# deska.net
KiCad netlist of a schematic drawn in EAGLE
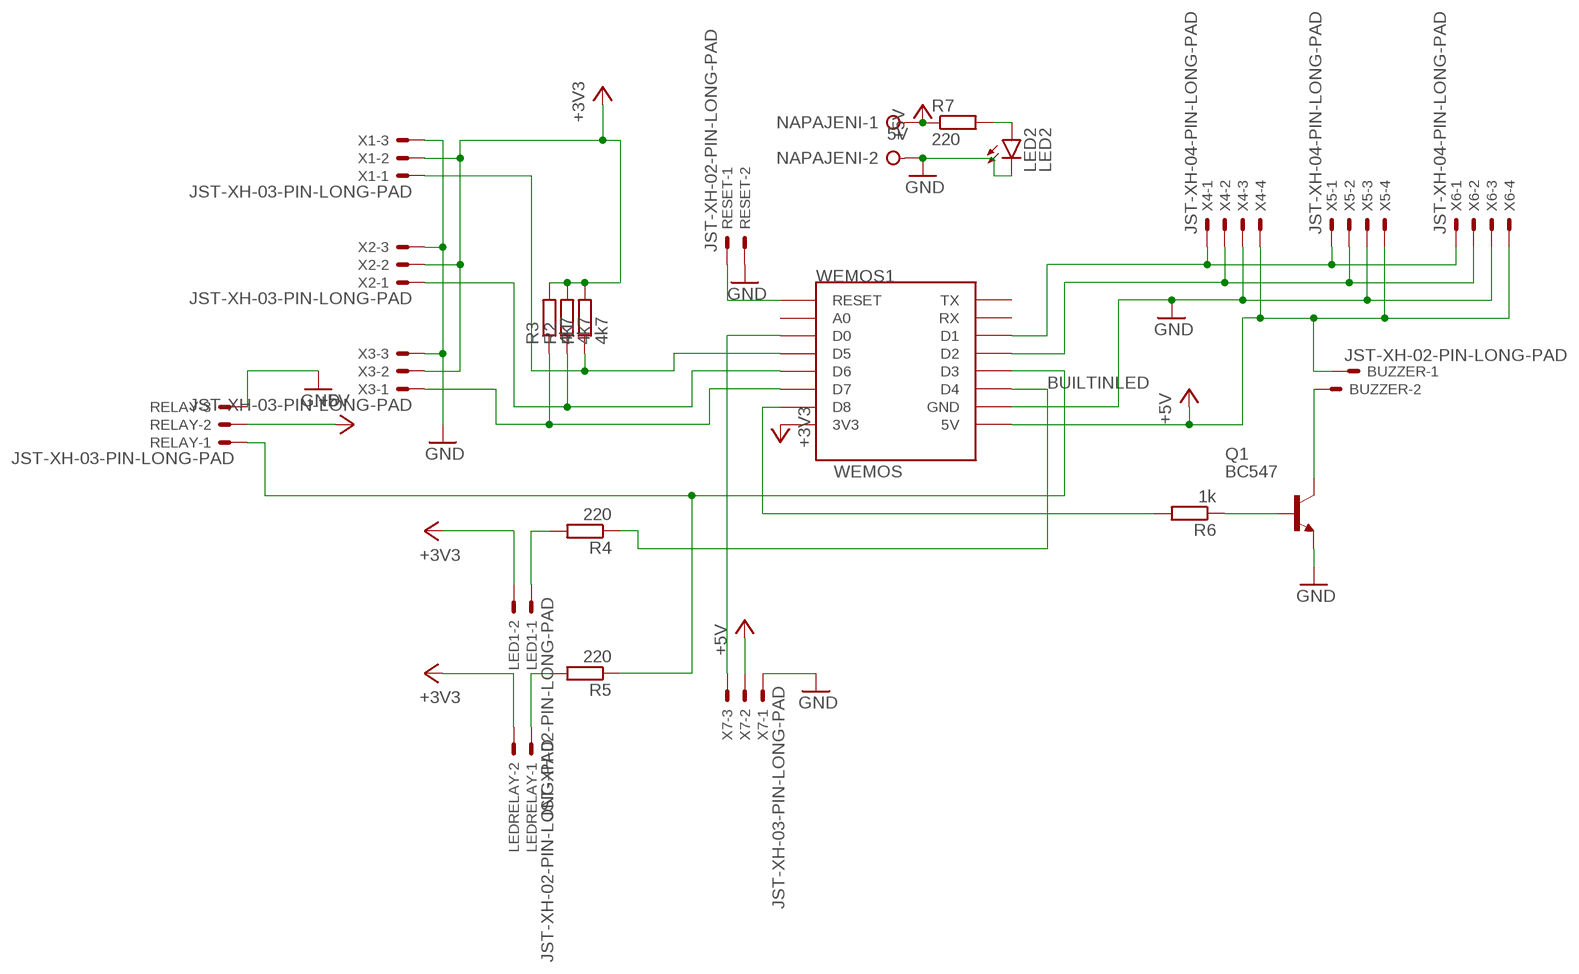
[diagram p0: schematic, sheet 1]

(export (version "E")
  (design (tool "Eeschema 10.0.6"))
  (components
    (comp (ref "BUZZER")
      (value "JST-XH-02-PIN-LONG-PAD")
      (footprint "eagle-import:JST-XH-02-PACKAGE-LONG-PAD")
      (libsource (lib "eagle-import") (part "JST-XH-02-PIN-LONG-PAD"))
    )
    (comp (ref "LED1")
      (value "JST-XH-02-PIN-LONG-PAD")
      (footprint "eagle-import:JST-XH-02-PACKAGE-LONG-PAD")
      (libsource (lib "eagle-import") (part "JST-XH-02-PIN-LONG-PAD"))
    )
    (comp (ref "LED2")
      (value "LED2")
      (footprint "eagle-import:LED3MM")
      (libsource (lib "eagle-import") (part "LED3MM"))
    )
    (comp (ref "LEDRELAY")
      (value "JST-XH-02-PIN-LONG-PAD")
      (footprint "eagle-import:JST-XH-02-PACKAGE-LONG-PAD")
      (libsource (lib "eagle-import") (part "JST-XH-02-PIN-LONG-PAD"))
    )
    (comp (ref "NAPAJENI")
      (value "5V")
      (footprint "eagle-import:W237-132")
      (libsource (lib "eagle-import") (part "W237-02P"))
    )
    (comp (ref "Q1")
      (value "BC547")
      (footprint "eagle-import:TO92")
      (libsource (lib "eagle-import") (part "BC547"))
    )
    (comp (ref "R1")
      (value "4k7")
      (footprint "eagle-import:0207_7")
      (libsource (lib "eagle-import") (part "R-EU_0207/7"))
    )
    (comp (ref "R2")
      (value "4k7")
      (footprint "eagle-import:0207_7")
      (libsource (lib "eagle-import") (part "R-EU_0207/7"))
    )
    (comp (ref "R3")
      (value "4k7")
      (footprint "eagle-import:0207_7")
      (libsource (lib "eagle-import") (part "R-EU_0207/7"))
    )
    (comp (ref "R4")
      (value "220")
      (footprint "eagle-import:0207_7")
      (libsource (lib "eagle-import") (part "R-EU_0207/7"))
    )
    (comp (ref "R5")
      (value "220")
      (footprint "eagle-import:0207_7")
      (libsource (lib "eagle-import") (part "R-EU_0207/7"))
    )
    (comp (ref "R6")
      (value "1k")
      (footprint "eagle-import:0207_7")
      (libsource (lib "eagle-import") (part "R-EU_0207/7"))
    )
    (comp (ref "R7")
      (value "220")
      (footprint "eagle-import:0207_7")
      (libsource (lib "eagle-import") (part "R-EU_0207/7"))
    )
    (comp (ref "RELAY")
      (value "JST-XH-03-PIN-LONG-PAD")
      (footprint "eagle-import:JST-XH-03-PACKAGE-LONG-PAD")
      (libsource (lib "eagle-import") (part "JST-XH-03-PIN-LONG-PAD"))
    )
    (comp (ref "RESET")
      (value "JST-XH-02-PIN-LONG-PAD")
      (footprint "eagle-import:JST-XH-02-PACKAGE-LONG-PAD")
      (libsource (lib "eagle-import") (part "JST-XH-02-PIN-LONG-PAD"))
    )
    (comp (ref "WEMOS1")
      (value "WEMOS")
      (footprint "eagle-import:WEMOS-D1-MINI")
      (libsource (lib "eagle-import") (part "WEMOS-D1-MINI"))
    )
    (comp (ref "X1")
      (value "JST-XH-03-PIN-LONG-PAD")
      (footprint "eagle-import:JST-XH-03-PACKAGE-LONG-PAD")
      (libsource (lib "eagle-import") (part "JST-XH-03-PIN-LONG-PAD"))
    )
    (comp (ref "X2")
      (value "JST-XH-03-PIN-LONG-PAD")
      (footprint "eagle-import:JST-XH-03-PACKAGE-LONG-PAD")
      (libsource (lib "eagle-import") (part "JST-XH-03-PIN-LONG-PAD"))
    )
    (comp (ref "X3")
      (value "JST-XH-03-PIN-LONG-PAD")
      (footprint "eagle-import:JST-XH-03-PACKAGE-LONG-PAD")
      (libsource (lib "eagle-import") (part "JST-XH-03-PIN-LONG-PAD"))
    )
    (comp (ref "X4")
      (value "JST-XH-04-PIN-LONG-PAD")
      (footprint "eagle-import:JST-XH-04-PACKAGE-LONG-PAD")
      (libsource (lib "eagle-import") (part "JST-XH-04-PIN-LONG-PAD"))
    )
    (comp (ref "X5")
      (value "JST-XH-04-PIN-LONG-PAD")
      (footprint "eagle-import:JST-XH-04-PACKAGE-LONG-PAD")
      (libsource (lib "eagle-import") (part "JST-XH-04-PIN-LONG-PAD"))
    )
    (comp (ref "X6")
      (value "JST-XH-04-PIN-LONG-PAD")
      (footprint "eagle-import:JST-XH-04-PACKAGE-LONG-PAD")
      (libsource (lib "eagle-import") (part "JST-XH-04-PIN-LONG-PAD"))
    )
    (comp (ref "X7")
      (value "JST-XH-03-PIN-LONG-PAD")
      (footprint "eagle-import:JST-XH-03-PACKAGE-LONG-PAD")
      (libsource (lib "eagle-import") (part "JST-XH-03-PIN-LONG-PAD"))
    )
  )
  (nets
    (net (code "1") (name "+3V3") (class "Default")
      (node (ref "LED1") (pin "2") (pinfunction "S_2") (pintype "passive"))
      (node (ref "LEDRELAY") (pin "2") (pinfunction "S_2") (pintype "passive"))
      (node (ref "R1") (pin "2") (pinfunction "2_2") (pintype "passive"))
      (node (ref "R2") (pin "2") (pinfunction "2_2") (pintype "passive"))
      (node (ref "R3") (pin "2") (pinfunction "2_2") (pintype "passive"))
      (node (ref "WEMOS1") (pin "3V3") (pinfunction "3V3_3V3") (pintype "bidirectional"))
      (node (ref "X1") (pin "2") (pinfunction "S_2") (pintype "passive"))
      (node (ref "X2") (pin "2") (pinfunction "S_2") (pintype "passive"))
      (node (ref "X3") (pin "2") (pinfunction "S_2") (pintype "passive"))
    )
    (net (code "2") (name "+5V") (class "Default")
      (node (ref "BUZZER") (pin "1") (pinfunction "S_1") (pintype "passive"))
      (node (ref "NAPAJENI") (pin "1") (pinfunction "KL_1") (pintype "passive"))
      (node (ref "R7") (pin "1") (pinfunction "1_1") (pintype "passive"))
      (node (ref "RELAY") (pin "2") (pinfunction "S_2") (pintype "passive"))
      (node (ref "WEMOS1") (pin "5V") (pinfunction "5V_5V") (pintype "bidirectional"))
      (node (ref "X4") (pin "4") (pinfunction "S_4") (pintype "passive"))
      (node (ref "X5") (pin "4") (pinfunction "S_4") (pintype "passive"))
      (node (ref "X6") (pin "4") (pinfunction "S_4") (pintype "passive"))
      (node (ref "X7") (pin "2") (pinfunction "S_2") (pintype "passive"))
    )
    (net (code "3") (name "/BUILTINLED") (class "Default")
      (node (ref "R4") (pin "1") (pinfunction "1_1") (pintype "passive"))
      (node (ref "WEMOS1") (pin "D4") (pinfunction "D4_D4") (pintype "bidirectional"))
    )
    (net (code "4") (name "GND") (class "Default")
      (node (ref "LED2") (pin "K") (pinfunction "C_K") (pintype "passive"))
      (node (ref "NAPAJENI") (pin "2") (pinfunction "KL_2") (pintype "passive"))
      (node (ref "Q1") (pin "1") (pinfunction "E_1") (pintype "passive"))
      (node (ref "RELAY") (pin "3") (pinfunction "S_3") (pintype "passive"))
      (node (ref "RESET") (pin "2") (pinfunction "S_2") (pintype "passive"))
      (node (ref "WEMOS1") (pin "GND") (pinfunction "GND_GND") (pintype "bidirectional"))
      (node (ref "X1") (pin "3") (pinfunction "S_3") (pintype "passive"))
      (node (ref "X2") (pin "3") (pinfunction "S_3") (pintype "passive"))
      (node (ref "X3") (pin "3") (pinfunction "S_3") (pintype "passive"))
      (node (ref "X4") (pin "3") (pinfunction "S_3") (pintype "passive"))
      (node (ref "X5") (pin "3") (pinfunction "S_3") (pintype "passive"))
      (node (ref "X6") (pin "3") (pinfunction "S_3") (pintype "passive"))
      (node (ref "X7") (pin "1") (pinfunction "S_1") (pintype "passive"))
    )
    (net (code "5") (name "Net-(BUZZERB-S)") (class "Default")
      (node (ref "BUZZER") (pin "2") (pinfunction "S_2") (pintype "passive"))
      (node (ref "Q1") (pin "3") (pinfunction "C_3") (pintype "passive"))
    )
    (net (code "6") (name "Net-(LED1A-S)") (class "Default")
      (node (ref "LED1") (pin "1") (pinfunction "S_1") (pintype "passive"))
      (node (ref "R4") (pin "2") (pinfunction "2_2") (pintype "passive"))
    )
    (net (code "7") (name "Net-(LED2-PadA)") (class "Default")
      (node (ref "LED2") (pin "A") (pinfunction "A_A") (pintype "passive"))
      (node (ref "R7") (pin "2") (pinfunction "2_2") (pintype "passive"))
    )
    (net (code "8") (name "Net-(LEDRELAYA-S)") (class "Default")
      (node (ref "LEDRELAY") (pin "1") (pinfunction "S_1") (pintype "passive"))
      (node (ref "R5") (pin "2") (pinfunction "2_2") (pintype "passive"))
    )
    (net (code "9") (name "Net-(Q1-B)") (class "Default")
      (node (ref "Q1") (pin "2") (pinfunction "B_2") (pintype "passive"))
      (node (ref "R6") (pin "1") (pinfunction "1_1") (pintype "passive"))
    )
    (net (code "10") (name "Net-(R6-Pad2)") (class "Default")
      (node (ref "R6") (pin "2") (pinfunction "2_2") (pintype "passive"))
      (node (ref "WEMOS1") (pin "D8") (pinfunction "D8_D8") (pintype "bidirectional"))
    )
    (net (code "11") (name "Net-(RELAYA-S)") (class "Default")
      (node (ref "R5") (pin "1") (pinfunction "1_1") (pintype "passive"))
      (node (ref "RELAY") (pin "1") (pinfunction "S_1") (pintype "passive"))
      (node (ref "WEMOS1") (pin "D3") (pinfunction "D3_D3") (pintype "bidirectional"))
    )
    (net (code "12") (name "Net-(RESETA-S)") (class "Default")
      (node (ref "RESET") (pin "1") (pinfunction "S_1") (pintype "passive"))
      (node (ref "WEMOS1") (pin "RESET") (pinfunction "RESET_RESET") (pintype "bidirectional"))
    )
    (net (code "13") (name "Net-(X1A-S)") (class "Default")
      (node (ref "R1") (pin "1") (pinfunction "1_1") (pintype "passive"))
      (node (ref "WEMOS1") (pin "D5") (pinfunction "D5_D5") (pintype "bidirectional"))
      (node (ref "X1") (pin "1") (pinfunction "S_1") (pintype "passive"))
    )
    (net (code "14") (name "Net-(X2A-S)") (class "Default")
      (node (ref "R2") (pin "1") (pinfunction "1_1") (pintype "passive"))
      (node (ref "WEMOS1") (pin "D6") (pinfunction "D6_D6") (pintype "bidirectional"))
      (node (ref "X2") (pin "1") (pinfunction "S_1") (pintype "passive"))
    )
    (net (code "15") (name "Net-(X3A-S)") (class "Default")
      (node (ref "R3") (pin "1") (pinfunction "1_1") (pintype "passive"))
      (node (ref "WEMOS1") (pin "D7") (pinfunction "D7_D7") (pintype "bidirectional"))
      (node (ref "X3") (pin "1") (pinfunction "S_1") (pintype "passive"))
    )
    (net (code "16") (name "Net-(X4A-S)") (class "Default")
      (node (ref "WEMOS1") (pin "D1") (pinfunction "D1_D1") (pintype "bidirectional"))
      (node (ref "X4") (pin "1") (pinfunction "S_1") (pintype "passive"))
      (node (ref "X5") (pin "1") (pinfunction "S_1") (pintype "passive"))
      (node (ref "X6") (pin "1") (pinfunction "S_1") (pintype "passive"))
    )
    (net (code "17") (name "Net-(X4B-S)") (class "Default")
      (node (ref "WEMOS1") (pin "D2") (pinfunction "D2_D2") (pintype "bidirectional"))
      (node (ref "X4") (pin "2") (pinfunction "S_2") (pintype "passive"))
      (node (ref "X5") (pin "2") (pinfunction "S_2") (pintype "passive"))
      (node (ref "X6") (pin "2") (pinfunction "S_2") (pintype "passive"))
    )
    (net (code "18") (name "Net-(X7C-S)") (class "Default")
      (node (ref "WEMOS1") (pin "D0") (pinfunction "D0_D0") (pintype "bidirectional"))
      (node (ref "X7") (pin "3") (pinfunction "S_3") (pintype "passive"))
    )
    (net (code "19") (name "unconnected-(WEMOS1-PadA0)") (class "Default")
      (node (ref "WEMOS1") (pin "A0") (pinfunction "A0_A0") (pintype "bidirectional"))
    )
    (net (code "20") (name "unconnected-(WEMOS1-PadRX)") (class "Default")
      (node (ref "WEMOS1") (pin "RX") (pinfunction "RX_RX") (pintype "bidirectional"))
    )
    (net (code "21") (name "unconnected-(WEMOS1-PadTX)") (class "Default")
      (node (ref "WEMOS1") (pin "TX") (pinfunction "TX_TX") (pintype "bidirectional"))
    )
  )
)
